# Battery.net
KiCad netlist of a schematic drawn in Altium Designer
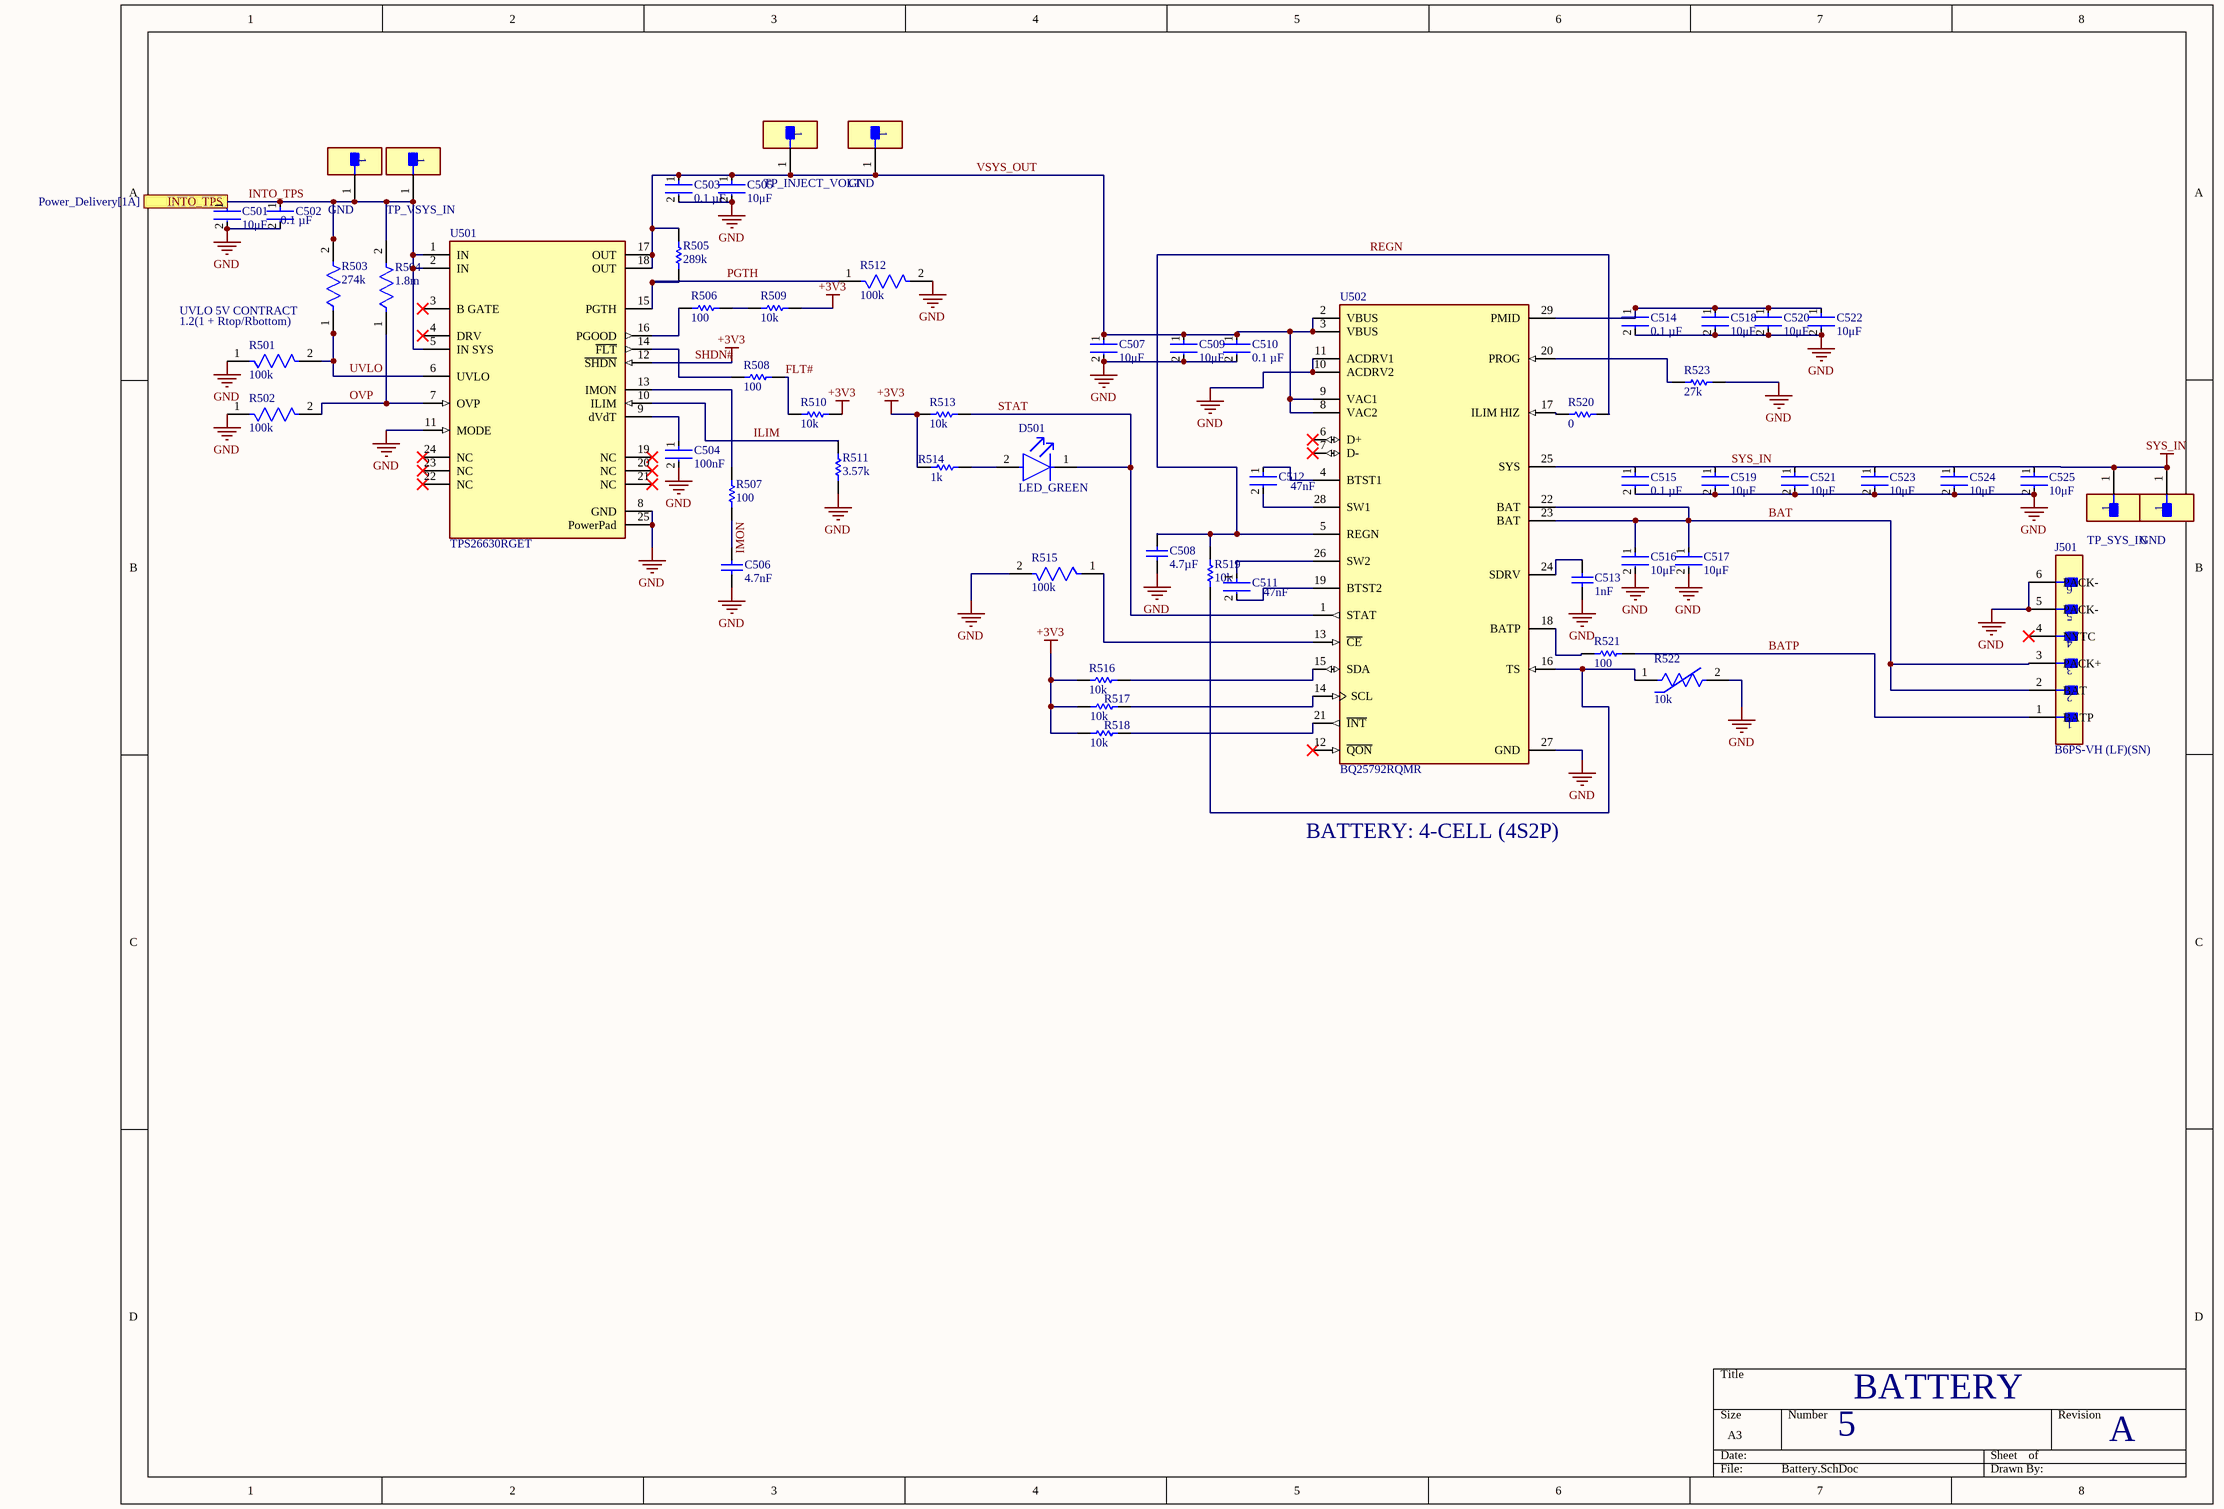
[diagram p0: Battery.SchDoc]

(export (version "E")
  (design (tool "Eeschema 10.0.6"))
  (components
    (comp (ref "C501")
      (value "10μF")
      (footprint "FP-GRM31C-0_2-e0_3_0_8-MFG")
      (description "Chip Multilayer Ceramic Capacitors for General Purpose, 1206, 10uF, X7R, 15%, 10%, 25V")
      (fields (field (name "TOLERANCE") "10%") (field (name "VOLTAGE") "25V"))
      (libsource (lib "Altium Content Vault") (part "02cd4be3c70576c341d710602a673aa"))
    )
    (comp (ref "C502")
      (value "0.1 µF")
      (footprint "FP-GRM155-0_05-IPC_B")
      (description "Chip Multilayer Ceramic Capacitors for General Purpose, 0402, 0.10uF, X7R, 15%, 10%, 50V")
      (fields (field (name "TOLERANCE") "10%"))
      (libsource (lib "Altium Content Vault") (part "02cd4be3c70576c341d710602a673aa"))
    )
    (comp (ref "C503")
      (value "0.1 µF")
      (footprint "FP-GRM155-0_05-IPC_B")
      (description "Chip Multilayer Ceramic Capacitors for General Purpose, 0402, 0.10uF, X7R, 15%, 10%, 50V")
      (fields (field (name "TOLERANCE") "10%"))
      (libsource (lib "Altium Content Vault") (part "02cd4be3c70576c341d710602a673aa"))
    )
    (comp (ref "C504")
      (value "100nF")
      (footprint "FP-GRM155-0_05-IPC_C")
      (description "Chip Multilayer Ceramic Capacitors for General Purpose, 0402, 0.10uF, X7R, 15%, 10%, 25V")
      (fields (field (name "TOLERANCE") "10%"))
      (libsource (lib "Altium Content Vault") (part "02cd4be3c70576c341d710602a673aa"))
    )
    (comp (ref "C505")
      (value "10μF")
      (footprint "FP-GRM31C-0_2-e0_3_0_8-MFG")
      (description "Chip Multilayer Ceramic Capacitors for General Purpose, 1206, 10uF, X7R, 15%, 10%, 25V")
      (fields (field (name "TOLERANCE") "10%") (field (name "VOLTAGE") "25V"))
      (libsource (lib "Altium Content Vault") (part "02cd4be3c70576c341d710602a673aa"))
    )
    (comp (ref "C506")
      (value "4.7nF")
      (footprint "CAPC1005X55X25LL05T10")
      (fields (field (name "MANUFACTURER") "Murata") (field (name "PART NUMBER") "GRM155R71C472KA01D"))
      (libsource (lib "Altium Content Vault") (part "CAP"))
    )
    (comp (ref "C507")
      (value "10μF")
      (footprint "FP-GRM31C-0_2-e0_3_0_8-MFG")
      (description "Chip Multilayer Ceramic Capacitors for General Purpose, 1206, 10uF, X7R, 15%, 10%, 25V")
      (fields (field (name "TOLERANCE") "10%") (field (name "VOLTAGE") "25V"))
      (libsource (lib "Altium Content Vault") (part "02cd4be3c70576c341d710602a673aa"))
    )
    (comp (ref "C508")
      (value "4.7µF")
      (footprint "CAPC1608X90X35NL10T15")
      (fields (field (name "MANUFACTURER") "Murata") (field (name "PART NUMBER") "GRM188R61A475KE15D"))
      (libsource (lib "Altium Content Vault") (part "CAP"))
    )
    (comp (ref "C509")
      (value "10μF")
      (footprint "FP-GRM31C-0_2-e0_3_0_8-MFG")
      (description "Chip Multilayer Ceramic Capacitors for General Purpose, 1206, 10uF, X7R, 15%, 10%, 25V")
      (fields (field (name "TOLERANCE") "10%") (field (name "VOLTAGE") "25V"))
      (libsource (lib "Altium Content Vault") (part "02cd4be3c70576c341d710602a673aa"))
    )
    (comp (ref "C510")
      (value "0.1 µF")
      (footprint "FP-GRM155-0_05-IPC_B")
      (description "Chip Multilayer Ceramic Capacitors for General Purpose, 0402, 0.10uF, X7R, 15%, 10%, 50V")
      (fields (field (name "TOLERANCE") "10%"))
      (libsource (lib "Altium Content Vault") (part "02cd4be3c70576c341d710602a673aa"))
    )
    (comp (ref "C511")
      (value "47nF")
      (footprint "FP-GRM155-0_05-MFG")
      (description "Chip Multilayer Ceramic Capacitors for General Purpose, 0402, 47000pF, X7R, 15%, 10%, 50V")
      (fields (field (name "TOLERANCE") "10%"))
      (libsource (lib "Altium Content Vault") (part "02cd4be3c70576c341d710602a673aa"))
    )
    (comp (ref "C512")
      (value "47nF")
      (footprint "FP-GRM155-0_05-MFG")
      (description "Chip Multilayer Ceramic Capacitors for General Purpose, 0402, 47000pF, X7R, 15%, 10%, 50V")
      (fields (field (name "TOLERANCE") "10%"))
      (libsource (lib "Altium Content Vault") (part "02cd4be3c70576c341d710602a673aa"))
    )
    (comp (ref "C513")
      (value "1nF")
      (footprint "CAPC1005X55X25ML5T10")
      (description "Chip Capacitor, 1 nF, +/- 10%, 50 V, -55 to 125 degC, 0402 (1005 Metric), RoHS, Tape and Reel")
      (fields (field (name "TOLERANCE") "10%"))
      (libsource (lib "Altium Content Vault") (part "CAP-NP-2"))
    )
    (comp (ref "C514")
      (value "0.1 µF")
      (footprint "FP-GRM155-0_05-IPC_B")
      (description "Chip Multilayer Ceramic Capacitors for General Purpose, 0402, 0.10uF, X7R, 15%, 10%, 50V")
      (fields (field (name "TOLERANCE") "10%"))
      (libsource (lib "Altium Content Vault") (part "02cd4be3c70576c341d710602a673aa"))
    )
    (comp (ref "C515")
      (value "0.1 µF")
      (footprint "FP-GRM155-0_05-IPC_B")
      (description "Chip Multilayer Ceramic Capacitors for General Purpose, 0402, 0.10uF, X7R, 15%, 10%, 50V")
      (fields (field (name "TOLERANCE") "10%"))
      (libsource (lib "Altium Content Vault") (part "02cd4be3c70576c341d710602a673aa"))
    )
    (comp (ref "C516")
      (value "10μF")
      (footprint "FP-GRM31C-0_2-e0_3_0_8-MFG")
      (description "Chip Multilayer Ceramic Capacitors for General Purpose, 1206, 10uF, X7R, 15%, 10%, 25V")
      (fields (field (name "TOLERANCE") "10%") (field (name "VOLTAGE") "25V"))
      (libsource (lib "Altium Content Vault") (part "02cd4be3c70576c341d710602a673aa"))
    )
    (comp (ref "C517")
      (value "10μF")
      (footprint "FP-GRM31C-0_2-e0_3_0_8-MFG")
      (description "Chip Multilayer Ceramic Capacitors for General Purpose, 1206, 10uF, X7R, 15%, 10%, 25V")
      (fields (field (name "TOLERANCE") "10%") (field (name "VOLTAGE") "25V"))
      (libsource (lib "Altium Content Vault") (part "02cd4be3c70576c341d710602a673aa"))
    )
    (comp (ref "C518")
      (value "10μF")
      (footprint "FP-GRM31C-0_2-e0_3_0_8-MFG")
      (description "Chip Multilayer Ceramic Capacitors for General Purpose, 1206, 10uF, X7R, 15%, 10%, 25V")
      (fields (field (name "TOLERANCE") "10%") (field (name "VOLTAGE") "25V"))
      (libsource (lib "Altium Content Vault") (part "02cd4be3c70576c341d710602a673aa"))
    )
    (comp (ref "C519")
      (value "10μF")
      (footprint "FP-GRM31C-0_2-e0_3_0_8-MFG")
      (description "Chip Multilayer Ceramic Capacitors for General Purpose, 1206, 10uF, X7R, 15%, 10%, 25V")
      (fields (field (name "TOLERANCE") "10%") (field (name "VOLTAGE") "25V"))
      (libsource (lib "Altium Content Vault") (part "02cd4be3c70576c341d710602a673aa"))
    )
    (comp (ref "C520")
      (value "10μF")
      (footprint "FP-GRM31C-0_2-e0_3_0_8-MFG")
      (description "Chip Multilayer Ceramic Capacitors for General Purpose, 1206, 10uF, X7R, 15%, 10%, 25V")
      (fields (field (name "TOLERANCE") "10%") (field (name "VOLTAGE") "25V"))
      (libsource (lib "Altium Content Vault") (part "02cd4be3c70576c341d710602a673aa"))
    )
    (comp (ref "C521")
      (value "10μF")
      (footprint "FP-GRM31C-0_2-e0_3_0_8-MFG")
      (description "Chip Multilayer Ceramic Capacitors for General Purpose, 1206, 10uF, X7R, 15%, 10%, 25V")
      (fields (field (name "TOLERANCE") "10%") (field (name "VOLTAGE") "25V"))
      (libsource (lib "Altium Content Vault") (part "02cd4be3c70576c341d710602a673aa"))
    )
    (comp (ref "C522")
      (value "10μF")
      (footprint "FP-GRM31C-0_2-e0_3_0_8-MFG")
      (description "Chip Multilayer Ceramic Capacitors for General Purpose, 1206, 10uF, X7R, 15%, 10%, 25V")
      (fields (field (name "TOLERANCE") "10%") (field (name "VOLTAGE") "25V"))
      (libsource (lib "Altium Content Vault") (part "02cd4be3c70576c341d710602a673aa"))
    )
    (comp (ref "C523")
      (value "10μF")
      (footprint "FP-GRM31C-0_2-e0_3_0_8-MFG")
      (description "Chip Multilayer Ceramic Capacitors for General Purpose, 1206, 10uF, X7R, 15%, 10%, 25V")
      (fields (field (name "TOLERANCE") "10%") (field (name "VOLTAGE") "25V"))
      (libsource (lib "Altium Content Vault") (part "02cd4be3c70576c341d710602a673aa"))
    )
    (comp (ref "C524")
      (value "10μF")
      (footprint "FP-GRM31C-0_2-e0_3_0_8-MFG")
      (description "Chip Multilayer Ceramic Capacitors for General Purpose, 1206, 10uF, X7R, 15%, 10%, 25V")
      (fields (field (name "TOLERANCE") "10%") (field (name "VOLTAGE") "25V"))
      (libsource (lib "Altium Content Vault") (part "02cd4be3c70576c341d710602a673aa"))
    )
    (comp (ref "C525")
      (value "10μF")
      (footprint "FP-GRM31C-0_2-e0_3_0_8-MFG")
      (description "Chip Multilayer Ceramic Capacitors for General Purpose, 1206, 10uF, X7R, 15%, 10%, 25V")
      (fields (field (name "TOLERANCE") "10%") (field (name "VOLTAGE") "25V"))
      (libsource (lib "Altium Content Vault") (part "02cd4be3c70576c341d710602a673aa"))
    )
    (comp (ref "D501")
      (value "LED_GREEN")
      (footprint "FP-SML-D12-MFG")
      (description "LED YLW/GREEN DIFFUSED 1608 SMD")
      (fields (field (name "MANUFACTURER PART NUMBER") "SML-D12M1WT86") (field (name "MANUFACTURER") "Rohm"))
      (libsource (lib "Altium Content Vault") (part "8706943c75ba83719d021d2fdc84c58"))
    )
    (comp (ref "J501")
      (value "B6PS-VH (LF)(SN)")
      (footprint "FP-B6PS-VH_LF_SN-MFG")
      (description "CONN HEADER R/A 6POS 3.96MM")
      (libsource (lib "Altium Content Vault") (part "f2cb566baf1c37ab5a3b8e90bbeafd6"))
    )
    (comp (ref "R501")
      (value "100k")
      (footprint "FP-RC0402-0_4-IPC_A")
      (description "RES 100K OHM 5% 1/16W 0402")
      (fields (field (name "TOLERANCE") "5%"))
      (libsource (lib "Altium Content Vault") (part "1029c3af85768c4190bb7ad29bc67b5"))
    )
    (comp (ref "R502")
      (value "100k")
      (footprint "FP-RC0402-0_4-IPC_A")
      (description "RES 100K OHM 5% 1/16W 0402")
      (fields (field (name "TOLERANCE") "5%"))
      (libsource (lib "Altium Content Vault") (part "1029c3af85768c4190bb7ad29bc67b5"))
    )
    (comp (ref "R503")
      (value "274k")
      (footprint "FP-AC0603-IPC_C")
      (description "RES 274KΩ 1.00% 0.1W 0603")
      (fields (field (name "TOLERANCE") "1%"))
      (libsource (lib "Altium Content Vault") (part "1029c3af85768c4190bb7ad29bc67b5"))
    )
    (comp (ref "R504")
      (value "1.8m")
      (footprint "FP-CRCW0402-e3-MFG")
      (description "RES Thick Film, 1.78MΩ, 1%, 0.063W, 100ppm/°C, 0402")
      (fields (field (name "TOLERANCE") "1%"))
      (libsource (lib "Altium Content Vault") (part "1029c3af85768c4190bb7ad29bc67b5"))
    )
    (comp (ref "R505")
      (value "289k")
      (footprint "RESC1005X40X25LL05T10")
      (fields (field (name "PART NUMBER") "RC0402FR-07287KL") (field (name "MANUFACTURER") "Yageo"))
      (libsource (lib "Altium Content Vault") (part "RES"))
    )
    (comp (ref "R506")
      (value "100")
      (footprint "RESC1005X40X25ML05T10")
      (fields (field (name "PART NUMBER") "RC0402FR-07100RL") (field (name "MANUFACTURER") "Yageo / Phycomp"))
      (libsource (lib "Altium Content Vault") (part "RES"))
    )
    (comp (ref "R507")
      (value "100")
      (footprint "RESC1005X40X25ML05T10")
      (fields (field (name "PART NUMBER") "RC0402FR-07100RL") (field (name "MANUFACTURER") "Yageo / Phycomp"))
      (libsource (lib "Altium Content Vault") (part "RES"))
    )
    (comp (ref "R508")
      (value "100")
      (footprint "RESC1005X40X25ML05T10")
      (fields (field (name "PART NUMBER") "RC0402FR-07100RL") (field (name "MANUFACTURER") "Yageo / Phycomp"))
      (libsource (lib "Altium Content Vault") (part "RES"))
    )
    (comp (ref "R509")
      (value "10k")
      (footprint "RESC1005X40X25LL05T10")
      (fields (field (name "PART NUMBER") "RC0402FR-0710KL") (field (name "MANUFACTURER") "Yageo / Phycomp"))
      (libsource (lib "Altium Content Vault") (part "RES"))
    )
    (comp (ref "R510")
      (value "10k")
      (footprint "RESC1005X40X25LL05T10")
      (fields (field (name "PART NUMBER") "RC0402FR-0710KL") (field (name "MANUFACTURER") "Yageo / Phycomp"))
      (libsource (lib "Altium Content Vault") (part "RES"))
    )
    (comp (ref "R511")
      (value "3.57k")
      (footprint "RESC1005X40X25ML05T10")
      (fields (field (name "PART NUMBER") "RC0402FR-073K57L") (field (name "MANUFACTURER") "Yageo"))
      (libsource (lib "Altium Content Vault") (part "RES"))
    )
    (comp (ref "R512")
      (value "100k")
      (footprint "FP-RC0402-0_4-IPC_A")
      (description "RES 100K OHM 5% 1/16W 0402")
      (fields (field (name "TOLERANCE") "5%"))
      (libsource (lib "Altium Content Vault") (part "1029c3af85768c4190bb7ad29bc67b5"))
    )
    (comp (ref "R513")
      (value "10k")
      (footprint "RESC1005X40X25LL05T10")
      (fields (field (name "PART NUMBER") "RC0402FR-0710KL") (field (name "MANUFACTURER") "Yageo / Phycomp"))
      (libsource (lib "Altium Content Vault") (part "RES"))
    )
    (comp (ref "R514")
      (value "1k")
      (footprint "RESC3216X60X45ML15T20")
      (description "Chip Resistor, 1 KOhm, +/- 1%, 0.25 W, -55 to 155 degC, 1206 (3216 Metric), RoHS, Tape and Reel")
      (fields (field (name "MANUFACTURER") "Vishay Semiconductor") (field (name "TOLERANCE") "1%"))
      (libsource (lib "Altium Content Vault") (part "RES-2"))
    )
    (comp (ref "R515")
      (value "100k")
      (footprint "FP-RC0402-0_4-IPC_A")
      (description "RES 100K OHM 5% 1/16W 0402")
      (fields (field (name "TOLERANCE") "5%"))
      (libsource (lib "Altium Content Vault") (part "1029c3af85768c4190bb7ad29bc67b5"))
    )
    (comp (ref "R516")
      (value "10k")
      (footprint "RESC1005X40X25LL05T10")
      (fields (field (name "PART NUMBER") "RC0402FR-0710KL") (field (name "MANUFACTURER") "Yageo / Phycomp"))
      (libsource (lib "Altium Content Vault") (part "RES"))
    )
    (comp (ref "R517")
      (value "10k")
      (footprint "RESC1005X40X25LL05T10")
      (fields (field (name "PART NUMBER") "RC0402FR-0710KL") (field (name "MANUFACTURER") "Yageo / Phycomp"))
      (libsource (lib "Altium Content Vault") (part "RES"))
    )
    (comp (ref "R518")
      (value "10k")
      (footprint "RESC1005X40X25LL05T10")
      (fields (field (name "PART NUMBER") "RC0402FR-0710KL") (field (name "MANUFACTURER") "Yageo / Phycomp"))
      (libsource (lib "Altium Content Vault") (part "RES"))
    )
    (comp (ref "R519")
      (value "10k")
      (footprint "RESC1005X40X25LL05T10")
      (fields (field (name "PART NUMBER") "RC0402FR-0710KL") (field (name "MANUFACTURER") "Yageo / Phycomp"))
      (libsource (lib "Altium Content Vault") (part "RES"))
    )
    (comp (ref "R520")
      (value "0")
      (footprint "RESC1005X40X25NL05T10")
      (fields (field (name "MANUFACTURER") "Yageo / Phycomp") (field (name "PART NUMBER") "RC0402JR-070RL"))
      (libsource (lib "Altium Content Vault") (part "RES"))
    )
    (comp (ref "R521")
      (value "100")
      (footprint "RESC1005X40X25ML05T10")
      (fields (field (name "PART NUMBER") "RC0402FR-07100RL") (field (name "MANUFACTURER") "Yageo / Phycomp"))
      (libsource (lib "Altium Content Vault") (part "RES"))
    )
    (comp (ref "R522")
      (value "10k")
      (footprint "FP-NCP15-NCU15-0_05-IPC_C")
      (description "NTC Thermistor for Temperature Sensor, 0402, 10kΩ, 1%, 0.1mA, 5V")
      (fields (field (name "TOLERANCE") "1%"))
      (libsource (lib "Altium Content Vault") (part "3b148a6ebabc5fb4d708a66c052d352"))
    )
    (comp (ref "R523")
      (value "27k")
      (footprint "RESC1005X40X25LL05T10")
      (fields (field (name "MANUFACTURER") "Yageo / Phycomp") (field (name "PART NUMBER") "RC0402FR-0727KL"))
      (libsource (lib "Altium Content Vault") (part "RES"))
    )
    (comp (ref "TP500")
      (value "GND")
      (footprint "FP-S2751-46R-MFG")
      (description "PC TEST POINT NATURAL")
      (libsource (lib "Altium Content Vault") (part "dd45045ce8184df9e99e12baf3f412c"))
    )
    (comp (ref "TP501")
      (value "TP_VSYS_IN")
      (footprint "FP-S2751-46R-MFG")
      (description "PC TEST POINT NATURAL")
      (libsource (lib "Altium Content Vault") (part "dd45045ce8184df9e99e12baf3f412c"))
    )
    (comp (ref "TP502")
      (value "TP_INJECT_VOLT")
      (footprint "FP-S2751-46R-MFG")
      (description "PC TEST POINT NATURAL")
      (libsource (lib "Altium Content Vault") (part "dd45045ce8184df9e99e12baf3f412c"))
    )
    (comp (ref "TP503")
      (value "GND")
      (footprint "FP-S2751-46R-MFG")
      (description "PC TEST POINT NATURAL")
      (libsource (lib "Altium Content Vault") (part "dd45045ce8184df9e99e12baf3f412c"))
    )
    (comp (ref "TP504")
      (value "TP_SYS_IN")
      (footprint "FP-S2751-46R-MFG")
      (description "PC TEST POINT NATURAL")
      (libsource (lib "") (part "dd45045ce8184df9e99e12baf3f412c_1"))
    )
    (comp (ref "TP505")
      (value "GND")
      (footprint "FP-S2751-46R-MFG")
      (description "PC TEST POINT NATURAL")
      (libsource (lib "") (part "dd45045ce8184df9e99e12baf3f412c_1"))
    )
    (comp (ref "U501")
      (value "TPS26630RGET")
      (footprint "FP-RGE0024H-MFG")
      (description "POWER MANAGEMENT")
      (libsource (lib "Altium Content Vault") (part "92e6325a0b2cd7354d0d77963e83935"))
    )
    (comp (ref "U502")
      (value "BQ25792RQMR")
      (footprint "FP-RQM0029A-MFG")
      (description "I2C CONTROLLED, 5-A, 1-4 CELL BU")
      (libsource (lib "Altium Content Vault") (part "43137d39c585c4e49e3b8f41bbae565"))
    )
  )
  (nets
    (net (code "1") (name "+3V3") (class "Default")
      (node (ref "R509") (pin "2") (pinfunction "2_2") (pintype "passive"))
      (node (ref "R510") (pin "2") (pinfunction "2_2") (pintype "passive"))
      (node (ref "R513") (pin "1") (pinfunction "1_1") (pintype "passive"))
      (node (ref "R514") (pin "2") (pinfunction "2_2") (pintype "passive"))
      (node (ref "R516") (pin "1") (pinfunction "1_1") (pintype "passive"))
      (node (ref "R517") (pin "1") (pinfunction "1_1") (pintype "passive"))
      (node (ref "R518") (pin "1") (pinfunction "1_1") (pintype "passive"))
      (node (ref "U501") (pin "12") (pinfunction "~{SHDN}_12") (pintype "input"))
    )
    (net (code "2") (name "/BAT") (class "Default")
      (node (ref "C516") (pin "1") (pinfunction "1_1") (pintype "passive"))
      (node (ref "C517") (pin "1") (pinfunction "1_1") (pintype "passive"))
      (node (ref "J501") (pin "2") (pinfunction "BAT_2") (pintype "passive"))
      (node (ref "J501") (pin "3") (pinfunction "PACK+_3") (pintype "passive"))
      (node (ref "U502") (pin "22") (pinfunction "BAT_22") (pintype "power_in"))
      (node (ref "U502") (pin "23") (pinfunction "BAT_23") (pintype "power_in"))
    )
    (net (code "3") (name "/BATP") (class "Default")
      (node (ref "J501") (pin "1") (pinfunction "BATP_1") (pintype "passive"))
      (node (ref "R521") (pin "2") (pinfunction "2_2") (pintype "passive"))
    )
    (net (code "4") (name "/FLT#") (class "Default")
      (node (ref "R508") (pin "2") (pinfunction "2_2") (pintype "passive"))
      (node (ref "R510") (pin "1") (pinfunction "1_1") (pintype "passive"))
    )
    (net (code "5") (name "/ILIM") (class "Default")
      (node (ref "R511") (pin "2") (pinfunction "2_2") (pintype "passive"))
      (node (ref "U501") (pin "10") (pinfunction "ILIM_10") (pintype "input"))
    )
    (net (code "6") (name "/IMON") (class "Default")
      (node (ref "C506") (pin "2") (pinfunction "2_2") (pintype "passive"))
      (node (ref "R507") (pin "1") (pinfunction "1_1") (pintype "passive"))
    )
    (net (code "7") (name "/INTO_TPS") (class "Default")
      (node (ref "C501") (pin "1") (pinfunction "1_1") (pintype "passive"))
      (node (ref "C502") (pin "1") (pinfunction "1_1") (pintype "passive"))
      (node (ref "R503") (pin "2") (pinfunction "2_2") (pintype "passive"))
      (node (ref "R504") (pin "2") (pinfunction "2_2") (pintype "passive"))
      (node (ref "TP500") (pin "1") (pinfunction "1_1") (pintype "passive"))
      (node (ref "TP501") (pin "1") (pinfunction "1_1") (pintype "passive"))
      (node (ref "U501") (pin "1") (pinfunction "IN_1") (pintype "power_in"))
      (node (ref "U501") (pin "2") (pinfunction "IN_2") (pintype "power_in"))
      (node (ref "U501") (pin "5") (pinfunction "IN_SYS_5") (pintype "power_in"))
    )
    (net (code "8") (name "/OVP") (class "Default")
      (node (ref "R502") (pin "2") (pinfunction "2_2") (pintype "passive"))
      (node (ref "R504") (pin "1") (pinfunction "1_1") (pintype "passive"))
      (node (ref "U501") (pin "7") (pinfunction "OVP_7") (pintype "input"))
    )
    (net (code "9") (name "/PGTH") (class "Default")
      (node (ref "R505") (pin "1") (pinfunction "1_1") (pintype "passive"))
      (node (ref "R512") (pin "1") (pinfunction "1_1") (pintype "passive"))
      (node (ref "U501") (pin "15") (pinfunction "PGTH_15") (pintype "passive"))
    )
    (net (code "10") (name "/REGN") (class "Default")
      (node (ref "C508") (pin "2") (pinfunction "2_2") (pintype "passive"))
      (node (ref "R519") (pin "1") (pinfunction "1_1") (pintype "passive"))
      (node (ref "R520") (pin "2") (pinfunction "2_2") (pintype "passive"))
      (node (ref "U502") (pin "5") (pinfunction "REGN_5") (pintype "power_in"))
    )
    (net (code "11") (name "/STAT") (class "Default")
      (node (ref "D501") (pin "1") (pinfunction "C_1") (pintype "passive"))
      (node (ref "R513") (pin "2") (pinfunction "2_2") (pintype "passive"))
      (node (ref "U502") (pin "1") (pinfunction "STAT_1") (pintype "output"))
    )
    (net (code "12") (name "/UVLO") (class "Default")
      (node (ref "R501") (pin "2") (pinfunction "2_2") (pintype "passive"))
      (node (ref "R503") (pin "1") (pinfunction "1_1") (pintype "passive"))
      (node (ref "U501") (pin "6") (pinfunction "UVLO_6") (pintype "passive"))
    )
    (net (code "13") (name "/VSYS_OUT") (class "Default")
      (node (ref "C503") (pin "1") (pinfunction "1_1") (pintype "passive"))
      (node (ref "C505") (pin "1") (pinfunction "1_1") (pintype "passive"))
      (node (ref "C507") (pin "1") (pinfunction "1_1") (pintype "passive"))
      (node (ref "C509") (pin "1") (pinfunction "1_1") (pintype "passive"))
      (node (ref "C510") (pin "1") (pinfunction "1_1") (pintype "passive"))
      (node (ref "R505") (pin "2") (pinfunction "2_2") (pintype "passive"))
      (node (ref "TP502") (pin "1") (pinfunction "1_1") (pintype "passive"))
      (node (ref "TP503") (pin "1") (pinfunction "1_1") (pintype "passive"))
      (node (ref "U501") (pin "17") (pinfunction "OUT_17") (pintype "power_in"))
      (node (ref "U501") (pin "18") (pinfunction "OUT_18") (pintype "power_in"))
      (node (ref "U502") (pin "2") (pinfunction "VBUS_2") (pintype "power_in"))
      (node (ref "U502") (pin "3") (pinfunction "VBUS_3") (pintype "power_in"))
      (node (ref "U502") (pin "8") (pinfunction "VAC2_8") (pintype "power_in"))
      (node (ref "U502") (pin "9") (pinfunction "VAC1_9") (pintype "power_in"))
    )
    (net (code "14") (name "GND") (class "Default")
      (node (ref "C501") (pin "2") (pinfunction "2_2") (pintype "passive"))
      (node (ref "C502") (pin "2") (pinfunction "2_2") (pintype "passive"))
      (node (ref "C503") (pin "2") (pinfunction "2_2") (pintype "passive"))
      (node (ref "C504") (pin "2") (pinfunction "2_2") (pintype "passive"))
      (node (ref "C505") (pin "2") (pinfunction "2_2") (pintype "passive"))
      (node (ref "C506") (pin "1") (pinfunction "1_1") (pintype "passive"))
      (node (ref "C507") (pin "2") (pinfunction "2_2") (pintype "passive"))
      (node (ref "C508") (pin "1") (pinfunction "1_1") (pintype "passive"))
      (node (ref "C509") (pin "2") (pinfunction "2_2") (pintype "passive"))
      (node (ref "C510") (pin "2") (pinfunction "2_2") (pintype "passive"))
      (node (ref "C513") (pin "1") (pinfunction "1_1") (pintype "passive"))
      (node (ref "C514") (pin "2") (pinfunction "2_2") (pintype "passive"))
      (node (ref "C515") (pin "2") (pinfunction "2_2") (pintype "passive"))
      (node (ref "C516") (pin "2") (pinfunction "2_2") (pintype "passive"))
      (node (ref "C517") (pin "2") (pinfunction "2_2") (pintype "passive"))
      (node (ref "C518") (pin "2") (pinfunction "2_2") (pintype "passive"))
      (node (ref "C519") (pin "2") (pinfunction "2_2") (pintype "passive"))
      (node (ref "C520") (pin "2") (pinfunction "2_2") (pintype "passive"))
      (node (ref "C521") (pin "2") (pinfunction "2_2") (pintype "passive"))
      (node (ref "C522") (pin "2") (pinfunction "2_2") (pintype "passive"))
      (node (ref "C523") (pin "2") (pinfunction "2_2") (pintype "passive"))
      (node (ref "C524") (pin "2") (pinfunction "2_2") (pintype "passive"))
      (node (ref "C525") (pin "2") (pinfunction "2_2") (pintype "passive"))
      (node (ref "J501") (pin "5") (pinfunction "PACK-_5") (pintype "passive"))
      (node (ref "J501") (pin "6") (pinfunction "PACK-_6") (pintype "passive"))
      (node (ref "R501") (pin "1") (pinfunction "1_1") (pintype "passive"))
      (node (ref "R502") (pin "1") (pinfunction "1_1") (pintype "passive"))
      (node (ref "R511") (pin "1") (pinfunction "1_1") (pintype "passive"))
      (node (ref "R512") (pin "2") (pinfunction "2_2") (pintype "passive"))
      (node (ref "R515") (pin "2") (pinfunction "2_2") (pintype "passive"))
      (node (ref "R522") (pin "2") (pinfunction "2_2") (pintype "passive"))
      (node (ref "R523") (pin "2") (pinfunction "2_2") (pintype "passive"))
      (node (ref "U501") (pin "11") (pinfunction "MODE_11") (pintype "input"))
      (node (ref "U501") (pin "25") (pinfunction "PowerPad_25") (pintype "power_in"))
      (node (ref "U501") (pin "8") (pinfunction "GND_8") (pintype "power_in"))
      (node (ref "U502") (pin "10") (pinfunction "ACDRV2_10") (pintype "power_in"))
      (node (ref "U502") (pin "11") (pinfunction "ACDRV1_11") (pintype "power_in"))
      (node (ref "U502") (pin "27") (pinfunction "GND_27") (pintype "power_in"))
    )
    (net (code "15") (name "Net-(D501-A)") (class "Default")
      (node (ref "D501") (pin "2") (pinfunction "A_2") (pintype "passive"))
      (node (ref "R514") (pin "1") (pinfunction "1_1") (pintype "passive"))
    )
    (net (code "16") (name "Net-(R506-Pad2)") (class "Default")
      (node (ref "R506") (pin "2") (pinfunction "2_2") (pintype "passive"))
      (node (ref "R509") (pin "1") (pinfunction "1_1") (pintype "passive"))
    )
    (net (code "17") (name "Net-(U501-IMON)") (class "Default")
      (node (ref "R507") (pin "2") (pinfunction "2_2") (pintype "passive"))
      (node (ref "U501") (pin "13") (pinfunction "IMON_13") (pintype "passive"))
    )
    (net (code "18") (name "Net-(U501-PGOOD)") (class "Default")
      (node (ref "R506") (pin "1") (pinfunction "1_1") (pintype "passive"))
      (node (ref "U501") (pin "16") (pinfunction "PGOOD_16") (pintype "output"))
    )
    (net (code "19") (name "Net-(U501-dVdT)") (class "Default")
      (node (ref "C504") (pin "1") (pinfunction "1_1") (pintype "passive"))
      (node (ref "U501") (pin "9") (pinfunction "dVdT_9") (pintype "passive"))
    )
    (net (code "20") (name "Net-(U501-~{FLT})") (class "Default")
      (node (ref "R508") (pin "1") (pinfunction "1_1") (pintype "passive"))
      (node (ref "U501") (pin "14") (pinfunction "~{FLT}_14") (pintype "output"))
    )
    (net (code "21") (name "Net-(U502-BATP)") (class "Default")
      (node (ref "R521") (pin "1") (pinfunction "1_1") (pintype "passive"))
      (node (ref "U502") (pin "18") (pinfunction "BATP_18") (pintype "power_in"))
    )
    (net (code "22") (name "Net-(U502-BTST1)") (class "Default")
      (node (ref "C512") (pin "1") (pinfunction "1_1") (pintype "passive"))
      (node (ref "U502") (pin "4") (pinfunction "BTST1_4") (pintype "power_in"))
    )
    (net (code "23") (name "Net-(U502-BTST2)") (class "Default")
      (node (ref "C511") (pin "2") (pinfunction "2_2") (pintype "passive"))
      (node (ref "U502") (pin "19") (pinfunction "BTST2_19") (pintype "power_in"))
    )
    (net (code "24") (name "Net-(U502-ILIM_HIZ)") (class "Default")
      (node (ref "R520") (pin "1") (pinfunction "1_1") (pintype "passive"))
      (node (ref "U502") (pin "17") (pinfunction "ILIM_HIZ_17") (pintype "input"))
    )
    (net (code "25") (name "Net-(U502-PMID)") (class "Default")
      (node (ref "C514") (pin "1") (pinfunction "1_1") (pintype "passive"))
      (node (ref "C518") (pin "1") (pinfunction "1_1") (pintype "passive"))
      (node (ref "C520") (pin "1") (pinfunction "1_1") (pintype "passive"))
      (node (ref "C522") (pin "1") (pinfunction "1_1") (pintype "passive"))
      (node (ref "U502") (pin "29") (pinfunction "PMID_29") (pintype "power_in"))
    )
    (net (code "26") (name "Net-(U502-PROG)") (class "Default")
      (node (ref "R523") (pin "1") (pinfunction "1_1") (pintype "passive"))
      (node (ref "U502") (pin "20") (pinfunction "PROG_20") (pintype "input"))
    )
    (net (code "27") (name "Net-(U502-SCL)") (class "Default")
      (node (ref "R517") (pin "2") (pinfunction "2_2") (pintype "passive"))
      (node (ref "U502") (pin "14") (pinfunction "SCL_14") (pintype "input"))
    )
    (net (code "28") (name "Net-(U502-SDA)") (class "Default")
      (node (ref "R516") (pin "2") (pinfunction "2_2") (pintype "passive"))
      (node (ref "U502") (pin "15") (pinfunction "SDA_15") (pintype "bidirectional"))
    )
    (net (code "29") (name "Net-(U502-SDRV)") (class "Default")
      (node (ref "C513") (pin "2") (pinfunction "2_2") (pintype "passive"))
      (node (ref "U502") (pin "24") (pinfunction "SDRV_24") (pintype "power_in"))
    )
    (net (code "30") (name "Net-(U502-SW1)") (class "Default")
      (node (ref "C512") (pin "2") (pinfunction "2_2") (pintype "passive"))
      (node (ref "U502") (pin "28") (pinfunction "SW1_28") (pintype "power_in"))
    )
    (net (code "31") (name "Net-(U502-SW2)") (class "Default")
      (node (ref "C511") (pin "1") (pinfunction "1_1") (pintype "passive"))
      (node (ref "U502") (pin "26") (pinfunction "SW2_26") (pintype "power_in"))
    )
    (net (code "32") (name "Net-(U502-TS)") (class "Default")
      (node (ref "R519") (pin "2") (pinfunction "2_2") (pintype "passive"))
      (node (ref "R522") (pin "1") (pinfunction "1_1") (pintype "passive"))
      (node (ref "U502") (pin "16") (pinfunction "TS_16") (pintype "input"))
    )
    (net (code "33") (name "Net-(U502-~{CE})") (class "Default")
      (node (ref "R515") (pin "1") (pinfunction "1_1") (pintype "passive"))
      (node (ref "U502") (pin "13") (pinfunction "~{CE}_13") (pintype "input"))
    )
    (net (code "34") (name "Net-(U502-~{INT})") (class "Default")
      (node (ref "R518") (pin "2") (pinfunction "2_2") (pintype "passive"))
      (node (ref "U502") (pin "21") (pinfunction "~{INT}_21") (pintype "output"))
    )
    (net (code "35") (name "SYS_IN") (class "Default")
      (node (ref "TP504") (pin "1") (pinfunction "1_1") (pintype "passive"))
      (node (ref "TP505") (pin "1") (pinfunction "1_1") (pintype "passive"))
      (node (ref "U502") (pin "25") (pinfunction "SYS_25") (pintype "power_in"))
    )
    (net (code "36") (name "unconnected-(C515-Pad1)") (class "Default")
      (node (ref "C515") (pin "1") (pinfunction "1_1") (pintype "passive"))
    )
    (net (code "37") (name "unconnected-(C519-Pad1)") (class "Default")
      (node (ref "C519") (pin "1") (pinfunction "1_1") (pintype "passive"))
    )
    (net (code "38") (name "unconnected-(C521-Pad1)") (class "Default")
      (node (ref "C521") (pin "1") (pinfunction "1_1") (pintype "passive"))
    )
    (net (code "39") (name "unconnected-(C523-Pad1)") (class "Default")
      (node (ref "C523") (pin "1") (pinfunction "1_1") (pintype "passive"))
    )
    (net (code "40") (name "unconnected-(C524-Pad1)") (class "Default")
      (node (ref "C524") (pin "1") (pinfunction "1_1") (pintype "passive"))
    )
    (net (code "41") (name "unconnected-(C525-Pad1)") (class "Default")
      (node (ref "C525") (pin "1") (pinfunction "1_1") (pintype "passive"))
    )
    (net (code "42") (name "unconnected-(J501-NYTC-Pad4)") (class "Default")
      (node (ref "J501") (pin "4") (pinfunction "NYTC_4") (pintype "passive+no_connect"))
    )
    (net (code "43") (name "unconnected-(U501-B_GATE-Pad3)") (class "Default")
      (node (ref "U501") (pin "3") (pinfunction "B_GATE_3") (pintype "passive+no_connect"))
    )
    (net (code "44") (name "unconnected-(U501-DRV-Pad4)") (class "Default")
      (node (ref "U501") (pin "4") (pinfunction "DRV_4") (pintype "passive+no_connect"))
    )
    (net (code "45") (name "unconnected-(U501-NC-Pad19)") (class "Default")
      (node (ref "U501") (pin "19") (pinfunction "NC_19") (pintype "passive+no_connect"))
    )
    (net (code "46") (name "unconnected-(U501-NC-Pad20)") (class "Default")
      (node (ref "U501") (pin "20") (pinfunction "NC_20") (pintype "passive+no_connect"))
    )
    (net (code "47") (name "unconnected-(U501-NC-Pad21)") (class "Default")
      (node (ref "U501") (pin "21") (pinfunction "NC_21") (pintype "passive+no_connect"))
    )
    (net (code "48") (name "unconnected-(U501-NC-Pad22)") (class "Default")
      (node (ref "U501") (pin "22") (pinfunction "NC_22") (pintype "passive+no_connect"))
    )
    (net (code "49") (name "unconnected-(U501-NC-Pad23)") (class "Default")
      (node (ref "U501") (pin "23") (pinfunction "NC_23") (pintype "passive+no_connect"))
    )
    (net (code "50") (name "unconnected-(U501-NC-Pad24)") (class "Default")
      (node (ref "U501") (pin "24") (pinfunction "NC_24") (pintype "passive+no_connect"))
    )
    (net (code "51") (name "unconnected-(U502-D+-Pad6)") (class "Default")
      (node (ref "U502") (pin "6") (pinfunction "D+_6") (pintype "bidirectional+no_connect"))
    )
    (net (code "52") (name "unconnected-(U502-D--Pad7)") (class "Default")
      (node (ref "U502") (pin "7") (pinfunction "D-_7") (pintype "bidirectional+no_connect"))
    )
    (net (code "53") (name "unconnected-(U502-~{QON}-Pad12)") (class "Default")
      (node (ref "U502") (pin "12") (pinfunction "~{QON}_12") (pintype "input+no_connect"))
    )
  )
)
